# Qwiic-Step.net
KiCad netlist of a schematic drawn in EAGLE
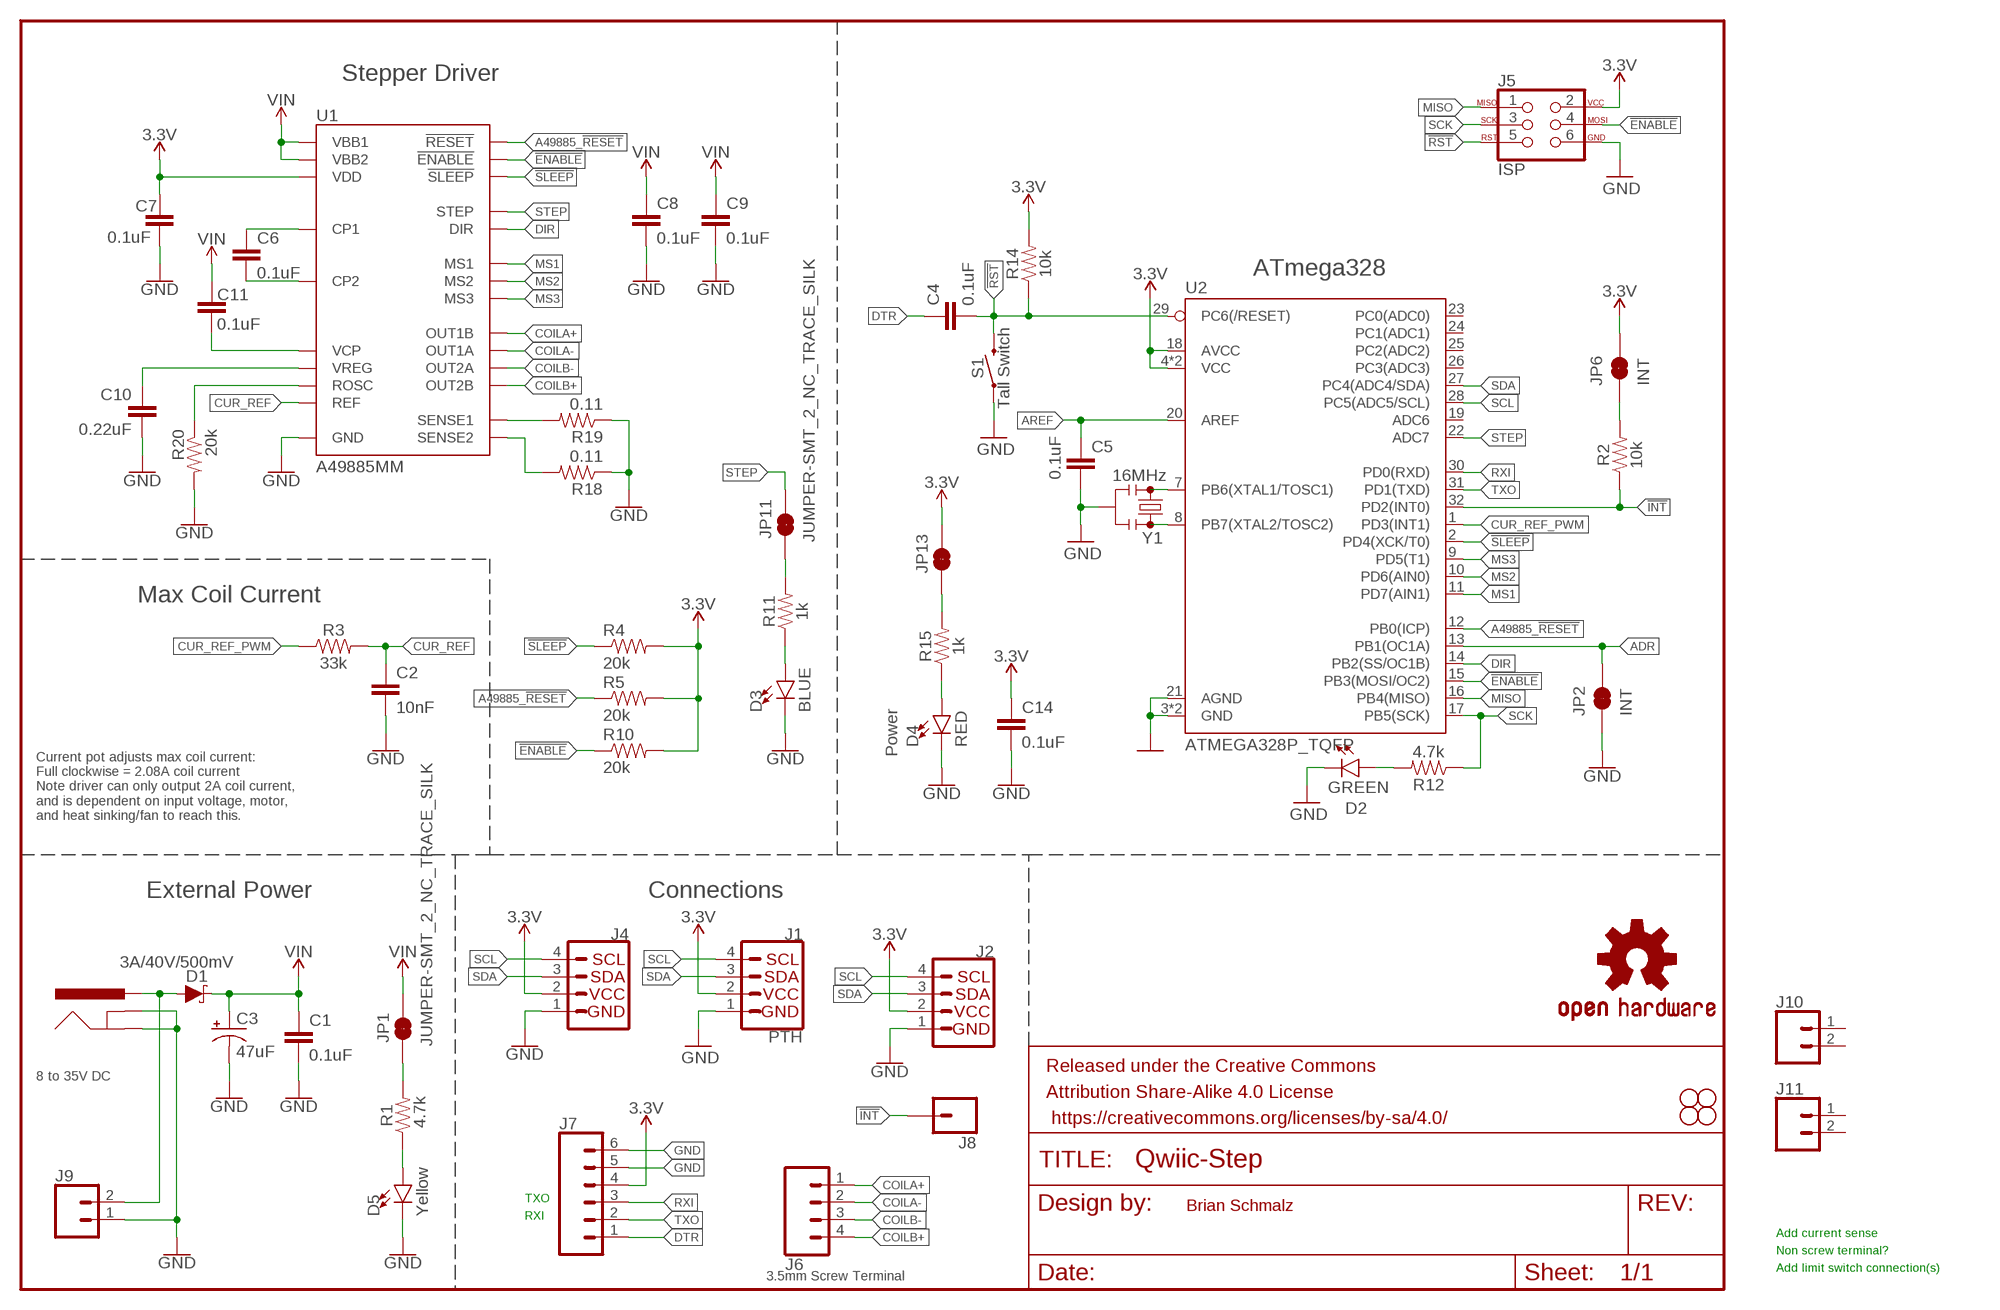
[diagram p0: schematic, sheet 1]

(export (version "E")
  (design (tool "Eeschema 10.0.6"))
  (components
    (comp (ref "C1")
      (value "0.1uF")
      (footprint "eagle-import:0603")
      (libsource (lib "eagle-import") (part "0.1UF-0603-100V-10%"))
    )
    (comp (ref "C2")
      (value "10nF")
      (footprint "eagle-import:0603")
      (libsource (lib "eagle-import") (part "10NF-0603-50V-10%"))
    )
    (comp (ref "C3")
      (value "47uF")
      (footprint "eagle-import:PANASONIC_D")
      (libsource (lib "eagle-import") (part "47UF-POLAR-PANASONIC_D-35V-20%"))
    )
    (comp (ref "C4")
      (value "0.1uF")
      (footprint "eagle-import:0603")
      (libsource (lib "eagle-import") (part "0.1UF-0603-100V-10%"))
    )
    (comp (ref "C5")
      (value "0.1uF")
      (footprint "eagle-import:0603")
      (libsource (lib "eagle-import") (part "0.1UF-0603-25V-(+80/-20%)"))
    )
    (comp (ref "C6")
      (value "0.1uF")
      (footprint "eagle-import:0603")
      (libsource (lib "eagle-import") (part "0.1UF-0603-100V-10%"))
    )
    (comp (ref "C7")
      (value "0.1uF")
      (footprint "eagle-import:0603")
      (libsource (lib "eagle-import") (part "0.1UF-0603-25V-(+80/-20%)"))
    )
    (comp (ref "C8")
      (value "0.1uF")
      (footprint "eagle-import:0603")
      (libsource (lib "eagle-import") (part "0.1UF-0603-100V-10%"))
    )
    (comp (ref "C9")
      (value "0.1uF")
      (footprint "eagle-import:0603")
      (libsource (lib "eagle-import") (part "0.1UF-0603-100V-10%"))
    )
    (comp (ref "C10")
      (value "0.22uF")
      (footprint "eagle-import:0603")
      (libsource (lib "eagle-import") (part "0.22UF-0603-50V-(-20/+80%)"))
    )
    (comp (ref "C11")
      (value "0.1uF")
      (footprint "eagle-import:0603")
      (libsource (lib "eagle-import") (part "0.1UF-0603-100V-10%"))
    )
    (comp (ref "C14")
      (value "0.1uF")
      (footprint "eagle-import:0603")
      (libsource (lib "eagle-import") (part "0.1UF-0603-25V-(+80/-20%)"))
    )
    (comp (ref "D1")
      (value "3A/40V/500mV")
      (footprint "eagle-import:SMA-DIODE")
      (libsource (lib "eagle-import") (part "DIODE-SCHOTTKY-B340A"))
    )
    (comp (ref "D2")
      (value "GREEN")
      (footprint "eagle-import:LED-0603")
      (libsource (lib "eagle-import") (part "LED-GREEN0603"))
    )
    (comp (ref "D3")
      (value "BLUE")
      (footprint "eagle-import:LED-0603")
      (libsource (lib "eagle-import") (part "LED-BLUE0603"))
    )
    (comp (ref "D4")
      (value "RED")
      (footprint "eagle-import:LED-0603")
      (libsource (lib "eagle-import") (part "LED-RED0603"))
    )
    (comp (ref "D5")
      (value "Yellow")
      (footprint "eagle-import:LED-0603")
      (libsource (lib "eagle-import") (part "LED-YELLOW0603"))
    )
    (comp (ref "FRAME1")
      (value "FRAME-LETTER")
      (footprint "eagle-import:CREATIVE_COMMONS")
      (libsource (lib "eagle-import") (part "FRAME-LETTER"))
    )
    (comp (ref "J1")
      (value "PTH")
      (footprint "eagle-import:1X04_NO_SILK")
      (libsource (lib "eagle-import") (part "SparkX_I2C_STANDARD_NO_SILK"))
    )
    (comp (ref "J2")
      (value "Qwiic Right Angle")
      (footprint "eagle-import:JST04_1MM_RA")
      (libsource (lib "eagle-import") (part "I2C_STANDARDQWIIC"))
    )
    (comp (ref "J3")
      (value "POWER_JACKSUPER_BOMB_DIGITY")
      (footprint "eagle-import:POWER_JACK_SMD_OVERPASTE_SUPER_BOMB_DIGITY")
      (libsource (lib "eagle-import") (part "POWER_JACKSUPER_BOMB_DIGITY"))
    )
    (comp (ref "J4")
      (value "Qwiic Right Angle")
      (footprint "eagle-import:JST04_1MM_RA")
      (libsource (lib "eagle-import") (part "I2C_STANDARDQWIIC"))
    )
    (comp (ref "J5")
      (value "ISP")
      (footprint "eagle-import:2X3_TEST_POINTS")
      (libsource (lib "eagle-import") (part "AVR_SPI_PROG_3X2TESTPOINTS"))
    )
    (comp (ref "J6")
      (value "CONN_04SCREW")
      (footprint "eagle-import:SCREWTERMINAL-3.5MM-4")
      (libsource (lib "eagle-import") (part "CONN_04SCREW"))
    )
    (comp (ref "J7")
      (value "CONN_06NO_SILK_NO_POP")
      (footprint "eagle-import:1X06_NO_SILK")
      (libsource (lib "eagle-import") (part "CONN_06NO_SILK_NO_POP"))
    )
    (comp (ref "J8")
      (value "CONN_01PTH_NO_SILK_YES_STOP")
      (footprint "eagle-import:1X01_NO_SILK")
      (libsource (lib "eagle-import") (part "CONN_01PTH_NO_SILK_YES_STOP"))
    )
    (comp (ref "J9")
      (value "CONN_023.5MM")
      (footprint "eagle-import:SCREWTERMINAL-3.5MM-2")
      (libsource (lib "eagle-import") (part "CONN_023.5MM"))
    )
    (comp (ref "J10")
      (value "CONN_02-JST-2MM-SMT")
      (footprint "eagle-import:JST-2-SMD")
      (libsource (lib "eagle-import") (part "CONN_02-JST-2MM-SMT"))
    )
    (comp (ref "J11")
      (value "CONN_02-JST-2MM-SMT")
      (footprint "eagle-import:JST-2-SMD")
      (libsource (lib "eagle-import") (part "CONN_02-JST-2MM-SMT"))
    )
    (comp (ref "JP1")
      (value "JUMPER-SMT_2_NC_TRACE_SILK")
      (footprint "eagle-import:SMT-JUMPER_2_NC_TRACE_SILK")
      (libsource (lib "eagle-import") (part "JUMPER-SMT_2_NC_TRACE_SILK"))
    )
    (comp (ref "JP2")
      (value "INT")
      (footprint "eagle-import:SMT-JUMPER_2_NC_TRACE_SILK")
      (libsource (lib "eagle-import") (part "JUMPER-SMT_2_NC_TRACE_SILK"))
    )
    (comp (ref "JP6")
      (value "INT")
      (footprint "eagle-import:SMT-JUMPER_2_NC_TRACE_SILK")
      (libsource (lib "eagle-import") (part "JUMPER-SMT_2_NC_TRACE_SILK"))
    )
    (comp (ref "JP7")
      (value "STAND-OFF")
      (footprint "eagle-import:STAND-OFF")
      (libsource (lib "eagle-import") (part "STAND-OFF"))
    )
    (comp (ref "JP8")
      (value "STAND-OFF")
      (footprint "eagle-import:STAND-OFF")
      (libsource (lib "eagle-import") (part "STAND-OFF"))
    )
    (comp (ref "JP9")
      (value "STAND-OFF")
      (footprint "eagle-import:STAND-OFF")
      (libsource (lib "eagle-import") (part "STAND-OFF"))
    )
    (comp (ref "JP10")
      (value "STAND-OFF")
      (footprint "eagle-import:STAND-OFF")
      (libsource (lib "eagle-import") (part "STAND-OFF"))
    )
    (comp (ref "JP11")
      (value "JUMPER-SMT_2_NC_TRACE_SILK")
      (footprint "eagle-import:SMT-JUMPER_2_NC_TRACE_SILK")
      (libsource (lib "eagle-import") (part "JUMPER-SMT_2_NC_TRACE_SILK"))
    )
    (comp (ref "JP13")
      (value "JUMPER-SMT_2_NC_TRACE_SILK")
      (footprint "eagle-import:SMT-JUMPER_2_NC_TRACE_SILK")
      (libsource (lib "eagle-import") (part "JUMPER-SMT_2_NC_TRACE_SILK"))
    )
    (comp (ref "LOGO1")
      (value "OSHW-LOGOMINI")
      (footprint "eagle-import:OSHW-LOGO-MINI")
      (libsource (lib "eagle-import") (part "OSHW-LOGOMINI"))
    )
    (comp (ref "R1")
      (value "4.7k")
      (footprint "eagle-import:0603")
      (libsource (lib "eagle-import") (part "4.7KOHM-0603-1/10W-1%"))
    )
    (comp (ref "R2")
      (value "10k")
      (footprint "eagle-import:0603")
      (libsource (lib "eagle-import") (part "10KOHM-0603-1/10W-1%"))
    )
    (comp (ref "R3")
      (value "33k")
      (footprint "eagle-import:0603")
      (libsource (lib "eagle-import") (part "33KOHM-0603-1/10W-1%"))
    )
    (comp (ref "R4")
      (value "20k")
      (footprint "eagle-import:0603")
      (libsource (lib "eagle-import") (part "20KOHM-0603-1/10W-1%"))
    )
    (comp (ref "R5")
      (value "20k")
      (footprint "eagle-import:0603")
      (libsource (lib "eagle-import") (part "20KOHM-0603-1/10W-1%"))
    )
    (comp (ref "R10")
      (value "20k")
      (footprint "eagle-import:0603")
      (libsource (lib "eagle-import") (part "20KOHM-0603-1/10W-1%"))
    )
    (comp (ref "R11")
      (value "1k")
      (footprint "eagle-import:0603")
      (libsource (lib "eagle-import") (part "1KOHM-0603-1/10W-1%"))
    )
    (comp (ref "R12")
      (value "4.7k")
      (footprint "eagle-import:0603")
      (libsource (lib "eagle-import") (part "4.7KOHM-0603-1/10W-1%"))
    )
    (comp (ref "R14")
      (value "10k")
      (footprint "eagle-import:0603")
      (libsource (lib "eagle-import") (part "10KOHM-0603-1/10W-1%"))
    )
    (comp (ref "R15")
      (value "1k")
      (footprint "eagle-import:0603")
      (libsource (lib "eagle-import") (part "1KOHM-0603-1/10W-1%"))
    )
    (comp (ref "R18")
      (value "0.11")
      (footprint "eagle-import:2010")
      (libsource (lib "eagle-import") (part "0.11OHM-2010-1/2W-1%"))
    )
    (comp (ref "R19")
      (value "0.11")
      (footprint "eagle-import:2010")
      (libsource (lib "eagle-import") (part "0.11OHM-2010-1/2W-1%"))
    )
    (comp (ref "R20")
      (value "20k")
      (footprint "eagle-import:0603")
      (libsource (lib "eagle-import") (part "20KOHM-0603-1/10W-1%"))
    )
    (comp (ref "S1")
      (value "Tall Switch")
      (footprint "eagle-import:TACTILE_SWITCH_SMD_5.2MM")
      (libsource (lib "eagle-import") (part "MOMENTARY-SWITCH-SPST-SMD-5.2-TALL-REDUNDANT"))
    )
    (comp (ref "U1")
      (value "A49885MM")
      (footprint "eagle-import:QFN-28-5MM")
      (libsource (lib "eagle-import") (part "A49885MM"))
    )
    (comp (ref "U2")
      (value "ATMEGA328P_TQFP")
      (footprint "eagle-import:TQFP32-08")
      (libsource (lib "eagle-import") (part "ATMEGA328P_TQFP"))
    )
    (comp (ref "Y1")
      (value "16MHz")
      (footprint "eagle-import:RESONATOR-SMD-3.2X1.3")
      (libsource (lib "eagle-import") (part "RESONATOR-16MHZSMD_3.2X1.3"))
    )
  )
  (nets
    (net (code "1") (name "/A49885_~{RESET}") (class "Default")
      (node (ref "R5") (pin "1") (pinfunction "1_1") (pintype "passive"))
      (node (ref "U1") (pin "12") (pinfunction "~{RESET}_12") (pintype "input"))
      (node (ref "U2") (pin "12") (pinfunction "PB0(ICP)_12") (pintype "bidirectional"))
    )
    (net (code "2") (name "/~{ENABLE}") (class "Default")
      (node (ref "J5") (pin "4") (pinfunction "4_4") (pintype "passive"))
      (node (ref "R10") (pin "1") (pinfunction "1_1") (pintype "passive"))
      (node (ref "U1") (pin "2") (pinfunction "~{ENABLE}_2") (pintype "input"))
      (node (ref "U2") (pin "15") (pinfunction "PB3(MOSI/OC2)_15") (pintype "bidirectional"))
    )
    (net (code "3") (name "/~{INT}") (class "Default")
      (node (ref "J8") (pin "1") (pinfunction "1_1") (pintype "passive"))
      (node (ref "R2") (pin "1") (pinfunction "1_1") (pintype "passive"))
      (node (ref "U2") (pin "32") (pinfunction "PD2(INT0)_32") (pintype "bidirectional"))
    )
    (net (code "4") (name "/~{RST}") (class "Default")
      (node (ref "C4") (pin "2") (pinfunction "2_2") (pintype "passive"))
      (node (ref "J5") (pin "5") (pinfunction "5_5") (pintype "passive"))
      (node (ref "R14") (pin "1") (pinfunction "1_1") (pintype "passive"))
      (node (ref "S1") (pin "3") (pinfunction "2_3") (pintype "passive"))
      (node (ref "S1") (pin "4") (pinfunction "2_4") (pintype "passive"))
      (node (ref "U2") (pin "29") (pinfunction "PC6(/RESET)_29") (pintype "bidirectional"))
    )
    (net (code "5") (name "/~{SLEEP}") (class "Default")
      (node (ref "R4") (pin "1") (pinfunction "1_1") (pintype "passive"))
      (node (ref "U1") (pin "14") (pinfunction "~{SLEEP}_14") (pintype "input"))
      (node (ref "U2") (pin "2") (pinfunction "PD4(XCK/T0)_2") (pintype "bidirectional"))
    )
    (net (code "6") (name "3.3V") (class "Default")
      (node (ref "C14") (pin "1") (pinfunction "1_1") (pintype "passive"))
      (node (ref "C7") (pin "1") (pinfunction "1_1") (pintype "passive"))
      (node (ref "J1") (pin "2") (pinfunction "VCC_2") (pintype "power_in"))
      (node (ref "J2") (pin "2") (pinfunction "2_2") (pintype "power_in"))
      (node (ref "J4") (pin "2") (pinfunction "2_2") (pintype "power_in"))
      (node (ref "J5") (pin "2") (pinfunction "2_2") (pintype "passive"))
      (node (ref "J7") (pin "4") (pinfunction "4_4") (pintype "passive"))
      (node (ref "JP13") (pin "2") (pinfunction "2_2") (pintype "passive"))
      (node (ref "JP6") (pin "2") (pinfunction "2_2") (pintype "passive"))
      (node (ref "R10") (pin "2") (pinfunction "2_2") (pintype "passive"))
      (node (ref "R14") (pin "2") (pinfunction "2_2") (pintype "passive"))
      (node (ref "R4") (pin "2") (pinfunction "2_2") (pintype "passive"))
      (node (ref "R5") (pin "2") (pinfunction "2_2") (pintype "passive"))
      (node (ref "U1") (pin "15") (pinfunction "VDD_15") (pintype "power_in"))
      (node (ref "U2") (pin "18") (pinfunction "AVCC_18") (pintype "bidirectional"))
      (node (ref "U2") (pin "4") (pinfunction "VCC_4") (pintype "bidirectional"))
      (node (ref "U2") (pin "6") (pinfunction "VCC_6") (pintype "bidirectional"))
    )
    (net (code "7") (name "ADR") (class "Default")
      (node (ref "JP2") (pin "2") (pinfunction "2_2") (pintype "passive"))
      (node (ref "U2") (pin "13") (pinfunction "PB1(OC1A)_13") (pintype "bidirectional"))
    )
    (net (code "8") (name "AREF") (class "Default")
      (node (ref "C5") (pin "1") (pinfunction "1_1") (pintype "passive"))
      (node (ref "U2") (pin "20") (pinfunction "AREF_20") (pintype "bidirectional"))
    )
    (net (code "9") (name "COILA+") (class "Default")
      (node (ref "J6") (pin "1") (pinfunction "1_1") (pintype "passive"))
      (node (ref "U1") (pin "21") (pinfunction "OUT1B_21") (pintype "bidirectional"))
    )
    (net (code "10") (name "COILA-") (class "Default")
      (node (ref "J6") (pin "2") (pinfunction "2_2") (pintype "passive"))
      (node (ref "U1") (pin "24") (pinfunction "OUT1A_24") (pintype "bidirectional"))
    )
    (net (code "11") (name "COILB+") (class "Default")
      (node (ref "J6") (pin "4") (pinfunction "4_4") (pintype "passive"))
      (node (ref "U1") (pin "1") (pinfunction "OUT2B_1") (pintype "bidirectional"))
    )
    (net (code "12") (name "COILB-") (class "Default")
      (node (ref "J6") (pin "3") (pinfunction "3_3") (pintype "passive"))
      (node (ref "U1") (pin "26") (pinfunction "OUT2A_26") (pintype "bidirectional"))
    )
    (net (code "13") (name "CUR_REF") (class "Default")
      (node (ref "C2") (pin "1") (pinfunction "1_1") (pintype "passive"))
      (node (ref "R3") (pin "2") (pinfunction "2_2") (pintype "passive"))
      (node (ref "U1") (pin "17") (pinfunction "REF_17") (pintype "bidirectional"))
    )
    (net (code "14") (name "CUR_REF_PWM") (class "Default")
      (node (ref "R3") (pin "1") (pinfunction "1_1") (pintype "passive"))
      (node (ref "U2") (pin "1") (pinfunction "PD3(INT1)_1") (pintype "bidirectional"))
    )
    (net (code "15") (name "DIR") (class "Default")
      (node (ref "U1") (pin "19") (pinfunction "DIR_19") (pintype "input"))
      (node (ref "U2") (pin "14") (pinfunction "PB2(SS/OC1B)_14") (pintype "bidirectional"))
    )
    (net (code "16") (name "DTR") (class "Default")
      (node (ref "C4") (pin "1") (pinfunction "1_1") (pintype "passive"))
      (node (ref "J7") (pin "1") (pinfunction "1_1") (pintype "passive"))
    )
    (net (code "17") (name "GND") (class "Default")
      (node (ref "C1") (pin "2") (pinfunction "2_2") (pintype "passive"))
      (node (ref "C10") (pin "2") (pinfunction "2_2") (pintype "passive"))
      (node (ref "C14") (pin "2") (pinfunction "2_2") (pintype "passive"))
      (node (ref "C2") (pin "2") (pinfunction "2_2") (pintype "passive"))
      (node (ref "C3") (pin "-") (pinfunction "-_-") (pintype "passive"))
      (node (ref "C5") (pin "2") (pinfunction "2_2") (pintype "passive"))
      (node (ref "C7") (pin "2") (pinfunction "2_2") (pintype "passive"))
      (node (ref "C8") (pin "2") (pinfunction "2_2") (pintype "passive"))
      (node (ref "C9") (pin "2") (pinfunction "2_2") (pintype "passive"))
      (node (ref "D2") (pin "C") (pinfunction "C_C") (pintype "passive"))
      (node (ref "D3") (pin "C") (pinfunction "C_C") (pintype "passive"))
      (node (ref "D4") (pin "C") (pinfunction "C_C") (pintype "passive"))
      (node (ref "D5") (pin "C") (pinfunction "C_C") (pintype "passive"))
      (node (ref "J1") (pin "1") (pinfunction "GND_1") (pintype "power_in"))
      (node (ref "J2") (pin "1") (pinfunction "1_1") (pintype "power_in"))
      (node (ref "J3") (pin "GND") (pinfunction "GNDBREAK_GND") (pintype "bidirectional"))
      (node (ref "J3") (pin "P$4") (pinfunction "GND_P$4") (pintype "bidirectional"))
      (node (ref "J4") (pin "1") (pinfunction "1_1") (pintype "power_in"))
      (node (ref "J5") (pin "6") (pinfunction "6_6") (pintype "passive"))
      (node (ref "J7") (pin "5") (pinfunction "5_5") (pintype "passive"))
      (node (ref "J7") (pin "6") (pinfunction "6_6") (pintype "passive"))
      (node (ref "J9") (pin "1") (pinfunction "1_1") (pintype "passive"))
      (node (ref "JP2") (pin "1") (pinfunction "1_1") (pintype "passive"))
      (node (ref "R18") (pin "1") (pinfunction "1_1") (pintype "passive"))
      (node (ref "R19") (pin "1") (pinfunction "1_1") (pintype "passive"))
      (node (ref "R20") (pin "2") (pinfunction "2_2") (pintype "passive"))
      (node (ref "S1") (pin "1") (pinfunction "1_1") (pintype "passive"))
      (node (ref "S1") (pin "2") (pinfunction "1_2") (pintype "passive"))
      (node (ref "U1") (pin "18") (pinfunction "GND_18") (pintype "power_in"))
      (node (ref "U1") (pin "29") (pinfunction "GND_29") (pintype "power_in"))
      (node (ref "U1") (pin "3") (pinfunction "GND_3") (pintype "power_in"))
      (node (ref "U2") (pin "21") (pinfunction "AGND_21") (pintype "bidirectional"))
      (node (ref "U2") (pin "3") (pinfunction "GND_3") (pintype "bidirectional"))
      (node (ref "U2") (pin "5") (pinfunction "GND_5") (pintype "bidirectional"))
      (node (ref "Y1") (pin "2") (pinfunction "2_2") (pintype "passive"))
    )
    (net (code "18") (name "MISO") (class "Default")
      (node (ref "J5") (pin "1") (pinfunction "1_1") (pintype "passive"))
      (node (ref "U2") (pin "16") (pinfunction "PB4(MISO)_16") (pintype "bidirectional"))
    )
    (net (code "19") (name "MS1") (class "Default")
      (node (ref "U1") (pin "9") (pinfunction "MS1_9") (pintype "input"))
      (node (ref "U2") (pin "11") (pinfunction "PD7(AIN1)_11") (pintype "bidirectional"))
    )
    (net (code "20") (name "MS2") (class "Default")
      (node (ref "U1") (pin "10") (pinfunction "MS2_10") (pintype "input"))
      (node (ref "U2") (pin "10") (pinfunction "PD6(AIN0)_10") (pintype "bidirectional"))
    )
    (net (code "21") (name "MS3") (class "Default")
      (node (ref "U1") (pin "11") (pinfunction "MS3_11") (pintype "input"))
      (node (ref "U2") (pin "9") (pinfunction "PD5(T1)_9") (pintype "bidirectional"))
    )
    (net (code "22") (name "Net-(D2-PadA)") (class "Default")
      (node (ref "D2") (pin "A") (pinfunction "A_A") (pintype "passive"))
      (node (ref "R12") (pin "2") (pinfunction "2_2") (pintype "passive"))
    )
    (net (code "23") (name "Net-(D3-PadA)") (class "Default")
      (node (ref "D3") (pin "A") (pinfunction "A_A") (pintype "passive"))
      (node (ref "R11") (pin "1") (pinfunction "1_1") (pintype "passive"))
    )
    (net (code "24") (name "Net-(D4-PadA)") (class "Default")
      (node (ref "D4") (pin "A") (pinfunction "A_A") (pintype "passive"))
      (node (ref "R15") (pin "1") (pinfunction "1_1") (pintype "passive"))
    )
    (net (code "25") (name "Net-(D5-PadA)") (class "Default")
      (node (ref "D5") (pin "A") (pinfunction "A_A") (pintype "passive"))
      (node (ref "R1") (pin "1") (pinfunction "1_1") (pintype "passive"))
    )
    (net (code "26") (name "Net-(J3-PWR)") (class "Default")
      (node (ref "D1") (pin "A") (pinfunction "A_A") (pintype "passive"))
      (node (ref "J3") (pin "VIN0") (pinfunction "PWR_VIN0") (pintype "bidirectional"))
      (node (ref "J9") (pin "2") (pinfunction "2_2") (pintype "passive"))
    )
    (net (code "27") (name "Net-(JP1-Pad1)") (class "Default")
      (node (ref "JP1") (pin "1") (pinfunction "1_1") (pintype "passive"))
      (node (ref "R1") (pin "2") (pinfunction "2_2") (pintype "passive"))
    )
    (net (code "28") (name "Net-(JP6-Pad1)") (class "Default")
      (node (ref "JP6") (pin "1") (pinfunction "1_1") (pintype "passive"))
      (node (ref "R2") (pin "2") (pinfunction "2_2") (pintype "passive"))
    )
    (net (code "29") (name "Net-(JP11-Pad1)") (class "Default")
      (node (ref "JP11") (pin "1") (pinfunction "1_1") (pintype "passive"))
      (node (ref "R11") (pin "2") (pinfunction "2_2") (pintype "passive"))
    )
    (net (code "30") (name "Net-(JP13-Pad1)") (class "Default")
      (node (ref "JP13") (pin "1") (pinfunction "1_1") (pintype "passive"))
      (node (ref "R15") (pin "2") (pinfunction "2_2") (pintype "passive"))
    )
    (net (code "31") (name "Net-(U1-CP1)") (class "Default")
      (node (ref "C6") (pin "1") (pinfunction "1_1") (pintype "passive"))
      (node (ref "U1") (pin "4") (pinfunction "CP1_4") (pintype "bidirectional"))
    )
    (net (code "32") (name "Net-(U1-CP2)") (class "Default")
      (node (ref "C6") (pin "2") (pinfunction "2_2") (pintype "passive"))
      (node (ref "U1") (pin "5") (pinfunction "CP2_5") (pintype "bidirectional"))
    )
    (net (code "33") (name "Net-(U1-ROSC)") (class "Default")
      (node (ref "R20") (pin "1") (pinfunction "1_1") (pintype "passive"))
      (node (ref "U1") (pin "13") (pinfunction "ROSC_13") (pintype "bidirectional"))
    )
    (net (code "34") (name "Net-(U1-SENSE1)") (class "Default")
      (node (ref "R19") (pin "2") (pinfunction "2_2") (pintype "passive"))
      (node (ref "U1") (pin "23") (pinfunction "SENSE1_23") (pintype "bidirectional"))
    )
    (net (code "35") (name "Net-(U1-SENSE2)") (class "Default")
      (node (ref "R18") (pin "2") (pinfunction "2_2") (pintype "passive"))
      (node (ref "U1") (pin "27") (pinfunction "SENSE2_27") (pintype "bidirectional"))
    )
    (net (code "36") (name "Net-(U1-VCP)") (class "Default")
      (node (ref "C11") (pin "1") (pinfunction "1_1") (pintype "passive"))
      (node (ref "U1") (pin "6") (pinfunction "VCP_6") (pintype "bidirectional"))
    )
    (net (code "37") (name "Net-(U1-VREG)") (class "Default")
      (node (ref "C10") (pin "1") (pinfunction "1_1") (pintype "passive"))
      (node (ref "U1") (pin "8") (pinfunction "VREG_8") (pintype "bidirectional"))
    )
    (net (code "38") (name "Net-(U2-PB6(XTAL1{slash}TOSC1))") (class "Default")
      (node (ref "U2") (pin "7") (pinfunction "PB6(XTAL1/TOSC1)_7") (pintype "bidirectional"))
      (node (ref "Y1") (pin "1") (pinfunction "1_1") (pintype "passive"))
    )
    (net (code "39") (name "Net-(U2-PB7(XTAL2{slash}TOSC2))") (class "Default")
      (node (ref "U2") (pin "8") (pinfunction "PB7(XTAL2/TOSC2)_8") (pintype "bidirectional"))
      (node (ref "Y1") (pin "3") (pinfunction "3_3") (pintype "passive"))
    )
    (net (code "40") (name "RXI") (class "Default")
      (node (ref "J7") (pin "3") (pinfunction "3_3") (pintype "passive"))
      (node (ref "U2") (pin "30") (pinfunction "PD0(RXD)_30") (pintype "bidirectional"))
    )
    (net (code "41") (name "SCK") (class "Default")
      (node (ref "J5") (pin "3") (pinfunction "3_3") (pintype "passive"))
      (node (ref "R12") (pin "1") (pinfunction "1_1") (pintype "passive"))
      (node (ref "U2") (pin "17") (pinfunction "PB5(SCK)_17") (pintype "bidirectional"))
    )
    (net (code "42") (name "SCL") (class "Default")
      (node (ref "J1") (pin "4") (pinfunction "SCL_4") (pintype "passive"))
      (node (ref "J2") (pin "4") (pinfunction "4_4") (pintype "passive"))
      (node (ref "J4") (pin "4") (pinfunction "4_4") (pintype "passive"))
      (node (ref "U2") (pin "28") (pinfunction "PC5(ADC5/SCL)_28") (pintype "bidirectional"))
    )
    (net (code "43") (name "SDA") (class "Default")
      (node (ref "J1") (pin "3") (pinfunction "SDA_3") (pintype "passive"))
      (node (ref "J2") (pin "3") (pinfunction "3_3") (pintype "passive"))
      (node (ref "J4") (pin "3") (pinfunction "3_3") (pintype "passive"))
      (node (ref "U2") (pin "27") (pinfunction "PC4(ADC4/SDA)_27") (pintype "bidirectional"))
    )
    (net (code "44") (name "STEP") (class "Default")
      (node (ref "JP11") (pin "2") (pinfunction "2_2") (pintype "passive"))
      (node (ref "U1") (pin "16") (pinfunction "STEP_16") (pintype "input"))
      (node (ref "U2") (pin "22") (pinfunction "ADC7_22") (pintype "bidirectional"))
    )
    (net (code "45") (name "TXO") (class "Default")
      (node (ref "J7") (pin "2") (pinfunction "2_2") (pintype "passive"))
      (node (ref "U2") (pin "31") (pinfunction "PD1(TXD)_31") (pintype "bidirectional"))
    )
    (net (code "46") (name "VIN") (class "Default")
      (node (ref "C1") (pin "1") (pinfunction "1_1") (pintype "passive"))
      (node (ref "C11") (pin "2") (pinfunction "2_2") (pintype "passive"))
      (node (ref "C3") (pin "+") (pinfunction "+_+") (pintype "passive"))
      (node (ref "C8") (pin "1") (pinfunction "1_1") (pintype "passive"))
      (node (ref "C9") (pin "1") (pinfunction "1_1") (pintype "passive"))
      (node (ref "D1") (pin "C") (pinfunction "C_C") (pintype "passive"))
      (node (ref "JP1") (pin "2") (pinfunction "2_2") (pintype "passive"))
      (node (ref "U1") (pin "22") (pinfunction "VBB1_22") (pintype "bidirectional"))
      (node (ref "U1") (pin "28") (pinfunction "VBB2_28") (pintype "bidirectional"))
    )
    (net (code "47") (name "unconnected-(J10-1-Pad2)") (class "Default")
      (node (ref "J10") (pin "2") (pinfunction "1_2") (pintype "passive"))
    )
    (net (code "48") (name "unconnected-(J10-2-Pad1)") (class "Default")
      (node (ref "J10") (pin "1") (pinfunction "2_1") (pintype "passive"))
    )
    (net (code "49") (name "unconnected-(J11-1-Pad2)") (class "Default")
      (node (ref "J11") (pin "2") (pinfunction "1_2") (pintype "passive"))
    )
    (net (code "50") (name "unconnected-(J11-2-Pad1)") (class "Default")
      (node (ref "J11") (pin "1") (pinfunction "2_1") (pintype "passive"))
    )
    (net (code "51") (name "unconnected-(U2-ADC6-Pad19)") (class "Default")
      (node (ref "U2") (pin "19") (pinfunction "ADC6_19") (pintype "bidirectional"))
    )
    (net (code "52") (name "unconnected-(U2-PC0(ADC0)-Pad23)") (class "Default")
      (node (ref "U2") (pin "23") (pinfunction "PC0(ADC0)_23") (pintype "bidirectional"))
    )
    (net (code "53") (name "unconnected-(U2-PC1(ADC1)-Pad24)") (class "Default")
      (node (ref "U2") (pin "24") (pinfunction "PC1(ADC1)_24") (pintype "bidirectional"))
    )
    (net (code "54") (name "unconnected-(U2-PC2(ADC2)-Pad25)") (class "Default")
      (node (ref "U2") (pin "25") (pinfunction "PC2(ADC2)_25") (pintype "bidirectional"))
    )
    (net (code "55") (name "unconnected-(U2-PC3(ADC3)-Pad26)") (class "Default")
      (node (ref "U2") (pin "26") (pinfunction "PC3(ADC3)_26") (pintype "bidirectional"))
    )
  )
)
